# main.net
KiCad netlist of a schematic drawn in EAGLE
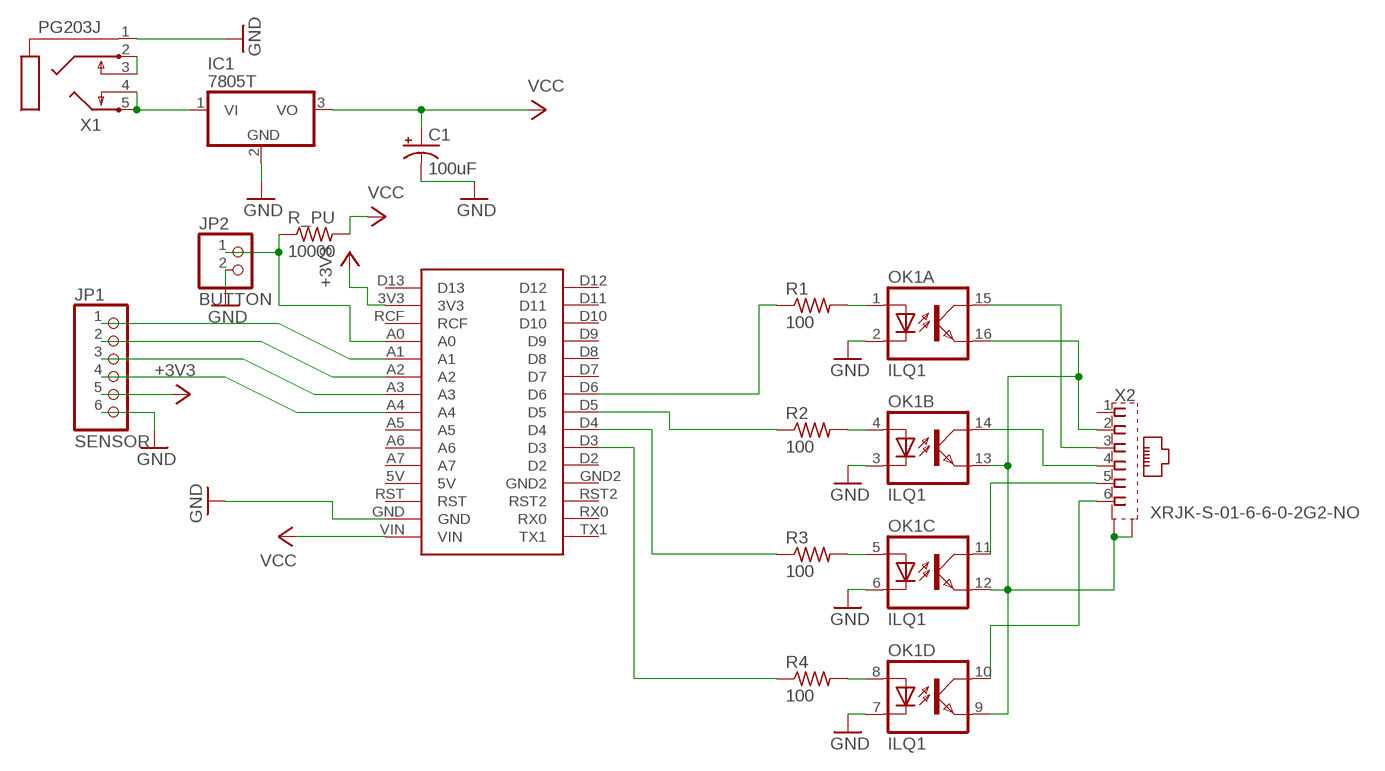
[diagram p0: schematic, sheet 1]

(export (version "E")
  (design (tool "Eeschema 10.0.6"))
  (components
    (comp (ref "C1")
      (value "100uF")
      (footprint "eagle-import:E2,5-6E")
      (libsource (lib "eagle-import") (part "CPOL-USE2,5-6E"))
    )
    (comp (ref "IC1")
      (value "7805T")
      (footprint "eagle-import:TO220H")
      (fields (field (name "MPN") "LM7805CT"))
      (libsource (lib "eagle-import") (part "78T05"))
    )
    (comp (ref "JP1")
      (value "SENSOR")
      (footprint "eagle-import:1X06")
      (libsource (lib "eagle-import") (part "PINHD-1X6"))
    )
    (comp (ref "JP2")
      (value "BUTTON")
      (footprint "eagle-import:1X02")
      (libsource (lib "eagle-import") (part "PINHD-1X2"))
    )
    (comp (ref "OK1")
      (value "ILQ1")
      (footprint "eagle-import:DIL16")
      (fields (field (name "MF") "VISHAY/TELEFUNKEN"))
      (libsource (lib "eagle-import") (part "ILQ1"))
    )
    (comp (ref "R1")
      (value "100")
      (footprint "eagle-import:0207_7")
      (libsource (lib "eagle-import") (part "R-US_0207/7"))
    )
    (comp (ref "R2")
      (value "100")
      (footprint "eagle-import:0207_7")
      (libsource (lib "eagle-import") (part "R-US_0207/7"))
    )
    (comp (ref "R3")
      (value "100")
      (footprint "eagle-import:0207_7")
      (libsource (lib "eagle-import") (part "R-US_0207/7"))
    )
    (comp (ref "R4")
      (value "100")
      (footprint "eagle-import:0207_7")
      (libsource (lib "eagle-import") (part "R-US_0207/7"))
    )
    (comp (ref "R_PU")
      (value "10000")
      (footprint "eagle-import:0207_7")
      (libsource (lib "eagle-import") (part "R-US_0207/7"))
    )
    (comp (ref "U$1")
      (value "ARDUINO_NANO_DEV")
      (footprint "eagle-import:NANO_PACK")
      (libsource (lib "eagle-import") (part "ARDUINO_NANO_DEV"))
    )
    (comp (ref "X1")
      (value "PG203J")
      (footprint "eagle-import:PG203J")
      (libsource (lib "eagle-import") (part "PG203J"))
    )
    (comp (ref "X2")
      (value "XRJK-S-01-6-6-0-2G2-NO")
      (footprint "eagle-import:XRJK-S-01-6-6-0-2G2-NO")
      (libsource (lib "eagle-import") (part "XRJK6-0-2G2-NO-S-01-6-"))
    )
  )
  (nets
    (net (code "1") (name "+3V3") (class "Default")
      (node (ref "JP1") (pin "5") (pinfunction "5_5") (pintype "passive"))
      (node (ref "U$1") (pin "3V3") (pinfunction "3V3_3V3") (pintype "bidirectional"))
    )
    (net (code "2") (name "GND") (class "Default")
      (node (ref "C1") (pin "-") (pinfunction "-_-") (pintype "passive"))
      (node (ref "IC1") (pin "2") (pinfunction "GND_2") (pintype "passive"))
      (node (ref "JP1") (pin "6") (pinfunction "6_6") (pintype "passive"))
      (node (ref "JP2") (pin "2") (pinfunction "2_2") (pintype "passive"))
      (node (ref "OK1") (pin "2") (pinfunction "C_2") (pintype "passive"))
      (node (ref "OK1") (pin "3") (pinfunction "C_3") (pintype "passive"))
      (node (ref "OK1") (pin "6") (pinfunction "C_6") (pintype "passive"))
      (node (ref "OK1") (pin "7") (pinfunction "C_7") (pintype "passive"))
      (node (ref "U$1") (pin "GND") (pinfunction "GND_GND") (pintype "bidirectional"))
      (node (ref "X1") (pin "1") (pinfunction "1_1") (pintype "passive"))
    )
    (net (code "3") (name "Net-(IC1-VI)") (class "Default")
      (node (ref "IC1") (pin "1") (pinfunction "VI_1") (pintype "input"))
      (node (ref "X1") (pin "4") (pinfunction "4_4") (pintype "passive"))
      (node (ref "X1") (pin "5") (pinfunction "5_5") (pintype "passive"))
    )
    (net (code "4") (name "Net-(JP1-Pad1)") (class "Default")
      (node (ref "JP1") (pin "1") (pinfunction "1_1") (pintype "passive"))
      (node (ref "U$1") (pin "A1") (pinfunction "A1_A1") (pintype "bidirectional"))
    )
    (net (code "5") (name "Net-(JP1-Pad2)") (class "Default")
      (node (ref "JP1") (pin "2") (pinfunction "2_2") (pintype "passive"))
      (node (ref "U$1") (pin "A2") (pinfunction "A2_A2") (pintype "bidirectional"))
    )
    (net (code "6") (name "Net-(JP1-Pad3)") (class "Default")
      (node (ref "JP1") (pin "3") (pinfunction "3_3") (pintype "passive"))
      (node (ref "U$1") (pin "A3") (pinfunction "A3_A3") (pintype "bidirectional"))
    )
    (net (code "7") (name "Net-(JP1-Pad4)") (class "Default")
      (node (ref "JP1") (pin "4") (pinfunction "4_4") (pintype "passive"))
      (node (ref "U$1") (pin "A4") (pinfunction "A4_A4") (pintype "bidirectional"))
    )
    (net (code "8") (name "Net-(JP2-Pad1)") (class "Default")
      (node (ref "JP2") (pin "1") (pinfunction "1_1") (pintype "passive"))
      (node (ref "R_PU") (pin "1") (pinfunction "1_1") (pintype "passive"))
      (node (ref "U$1") (pin "A0") (pinfunction "A0_A0") (pintype "bidirectional"))
    )
    (net (code "9") (name "Net-(OK1A-A)") (class "Default")
      (node (ref "OK1") (pin "1") (pinfunction "A_1") (pintype "passive"))
      (node (ref "R1") (pin "2") (pinfunction "2_2") (pintype "passive"))
    )
    (net (code "10") (name "Net-(OK1A-COL)") (class "Default")
      (node (ref "OK1") (pin "15") (pinfunction "COL_15") (pintype "passive"))
      (node (ref "X2") (pin "3") (pinfunction "3_3") (pintype "passive"))
    )
    (net (code "11") (name "Net-(OK1A-EMIT)") (class "Default")
      (node (ref "OK1") (pin "12") (pinfunction "EMIT_12") (pintype "passive"))
      (node (ref "OK1") (pin "13") (pinfunction "EMIT_13") (pintype "passive"))
      (node (ref "OK1") (pin "16") (pinfunction "EMIT_16") (pintype "passive"))
      (node (ref "OK1") (pin "9") (pinfunction "EMIT_9") (pintype "passive"))
      (node (ref "X2") (pin "2") (pinfunction "2_2") (pintype "passive"))
      (node (ref "X2") (pin "S1") (pinfunction "S_S1") (pintype "passive"))
      (node (ref "X2") (pin "S2") (pinfunction "S_S2") (pintype "passive"))
    )
    (net (code "12") (name "Net-(OK1B-A)") (class "Default")
      (node (ref "OK1") (pin "4") (pinfunction "A_4") (pintype "passive"))
      (node (ref "R2") (pin "2") (pinfunction "2_2") (pintype "passive"))
    )
    (net (code "13") (name "Net-(OK1B-COL)") (class "Default")
      (node (ref "OK1") (pin "14") (pinfunction "COL_14") (pintype "passive"))
      (node (ref "X2") (pin "4") (pinfunction "4_4") (pintype "passive"))
    )
    (net (code "14") (name "Net-(OK1C-A)") (class "Default")
      (node (ref "OK1") (pin "5") (pinfunction "A_5") (pintype "passive"))
      (node (ref "R3") (pin "2") (pinfunction "2_2") (pintype "passive"))
    )
    (net (code "15") (name "Net-(OK1C-COL)") (class "Default")
      (node (ref "OK1") (pin "11") (pinfunction "COL_11") (pintype "passive"))
      (node (ref "X2") (pin "5") (pinfunction "5_5") (pintype "passive"))
    )
    (net (code "16") (name "Net-(OK1D-A)") (class "Default")
      (node (ref "OK1") (pin "8") (pinfunction "A_8") (pintype "passive"))
      (node (ref "R4") (pin "2") (pinfunction "2_2") (pintype "passive"))
    )
    (net (code "17") (name "Net-(OK1D-COL)") (class "Default")
      (node (ref "OK1") (pin "10") (pinfunction "COL_10") (pintype "passive"))
      (node (ref "X2") (pin "6") (pinfunction "6_6") (pintype "passive"))
    )
    (net (code "18") (name "Net-(R1-Pad1)") (class "Default")
      (node (ref "R1") (pin "1") (pinfunction "1_1") (pintype "passive"))
      (node (ref "U$1") (pin "D6") (pinfunction "D6_D6") (pintype "bidirectional"))
    )
    (net (code "19") (name "Net-(R2-Pad1)") (class "Default")
      (node (ref "R2") (pin "1") (pinfunction "1_1") (pintype "passive"))
      (node (ref "U$1") (pin "D5") (pinfunction "D5_D5") (pintype "bidirectional"))
    )
    (net (code "20") (name "Net-(R3-Pad1)") (class "Default")
      (node (ref "R3") (pin "1") (pinfunction "1_1") (pintype "passive"))
      (node (ref "U$1") (pin "D4") (pinfunction "D4_D4") (pintype "bidirectional"))
    )
    (net (code "21") (name "Net-(R4-Pad1)") (class "Default")
      (node (ref "R4") (pin "1") (pinfunction "1_1") (pintype "passive"))
      (node (ref "U$1") (pin "D3") (pinfunction "D3_D3") (pintype "bidirectional"))
    )
    (net (code "22") (name "Net-(X1-Pad2)") (class "Default")
      (node (ref "X1") (pin "2") (pinfunction "2_2") (pintype "passive"))
      (node (ref "X1") (pin "3") (pinfunction "3_3") (pintype "passive"))
    )
    (net (code "23") (name "VCC") (class "Default")
      (node (ref "C1") (pin "+") (pinfunction "+_+") (pintype "passive"))
      (node (ref "IC1") (pin "3") (pinfunction "VO_3") (pintype "passive"))
      (node (ref "R_PU") (pin "2") (pinfunction "2_2") (pintype "passive"))
      (node (ref "U$1") (pin "VIN") (pinfunction "VIN_VIN") (pintype "bidirectional"))
    )
    (net (code "24") (name "unconnected-(U$1-Pad5V)") (class "Default")
      (node (ref "U$1") (pin "5V") (pinfunction "5V_5V") (pintype "bidirectional"))
    )
    (net (code "25") (name "unconnected-(U$1-PadA5)") (class "Default")
      (node (ref "U$1") (pin "A5") (pinfunction "A5_A5") (pintype "bidirectional"))
    )
    (net (code "26") (name "unconnected-(U$1-PadA6)") (class "Default")
      (node (ref "U$1") (pin "A6") (pinfunction "A6_A6") (pintype "bidirectional"))
    )
    (net (code "27") (name "unconnected-(U$1-PadA7)") (class "Default")
      (node (ref "U$1") (pin "A7") (pinfunction "A7_A7") (pintype "bidirectional"))
    )
    (net (code "28") (name "unconnected-(U$1-PadD2)") (class "Default")
      (node (ref "U$1") (pin "D2") (pinfunction "D2_D2") (pintype "bidirectional"))
    )
    (net (code "29") (name "unconnected-(U$1-PadD7)") (class "Default")
      (node (ref "U$1") (pin "D7") (pinfunction "D7_D7") (pintype "bidirectional"))
    )
    (net (code "30") (name "unconnected-(U$1-PadD8)") (class "Default")
      (node (ref "U$1") (pin "D8") (pinfunction "D8_D8") (pintype "bidirectional"))
    )
    (net (code "31") (name "unconnected-(U$1-PadD9)") (class "Default")
      (node (ref "U$1") (pin "D9") (pinfunction "D9_D9") (pintype "bidirectional"))
    )
    (net (code "32") (name "unconnected-(U$1-PadD10)") (class "Default")
      (node (ref "U$1") (pin "D10") (pinfunction "D10_D10") (pintype "bidirectional"))
    )
    (net (code "33") (name "unconnected-(U$1-PadD11)") (class "Default")
      (node (ref "U$1") (pin "D11") (pinfunction "D11_D11") (pintype "bidirectional"))
    )
    (net (code "34") (name "unconnected-(U$1-PadD12)") (class "Default")
      (node (ref "U$1") (pin "D12") (pinfunction "D12_D12") (pintype "bidirectional"))
    )
    (net (code "35") (name "unconnected-(U$1-PadD13)") (class "Default")
      (node (ref "U$1") (pin "D13") (pinfunction "D13_D13") (pintype "bidirectional"))
    )
    (net (code "36") (name "unconnected-(U$1-PadGND2)") (class "Default")
      (node (ref "U$1") (pin "GND2") (pinfunction "GND2_GND2") (pintype "bidirectional"))
    )
    (net (code "37") (name "unconnected-(U$1-PadRCF)") (class "Default")
      (node (ref "U$1") (pin "RCF") (pinfunction "RCF_RCF") (pintype "bidirectional"))
    )
    (net (code "38") (name "unconnected-(U$1-PadRST)") (class "Default")
      (node (ref "U$1") (pin "RST") (pinfunction "RST_RST") (pintype "bidirectional"))
    )
    (net (code "39") (name "unconnected-(U$1-PadRST2)") (class "Default")
      (node (ref "U$1") (pin "RST2") (pinfunction "RST2_RST2") (pintype "bidirectional"))
    )
    (net (code "40") (name "unconnected-(U$1-PadRX0)") (class "Default")
      (node (ref "U$1") (pin "RX0") (pinfunction "RX0_RX0") (pintype "bidirectional"))
    )
    (net (code "41") (name "unconnected-(U$1-PadTX1)") (class "Default")
      (node (ref "U$1") (pin "TX1") (pinfunction "TX1_TX1") (pintype "bidirectional"))
    )
    (net (code "42") (name "unconnected-(X2-Pad1)") (class "Default")
      (node (ref "X2") (pin "1") (pinfunction "1_1") (pintype "passive"))
    )
  )
)
